# ArduinoShield.net
KiCad netlist of a schematic drawn in EAGLE
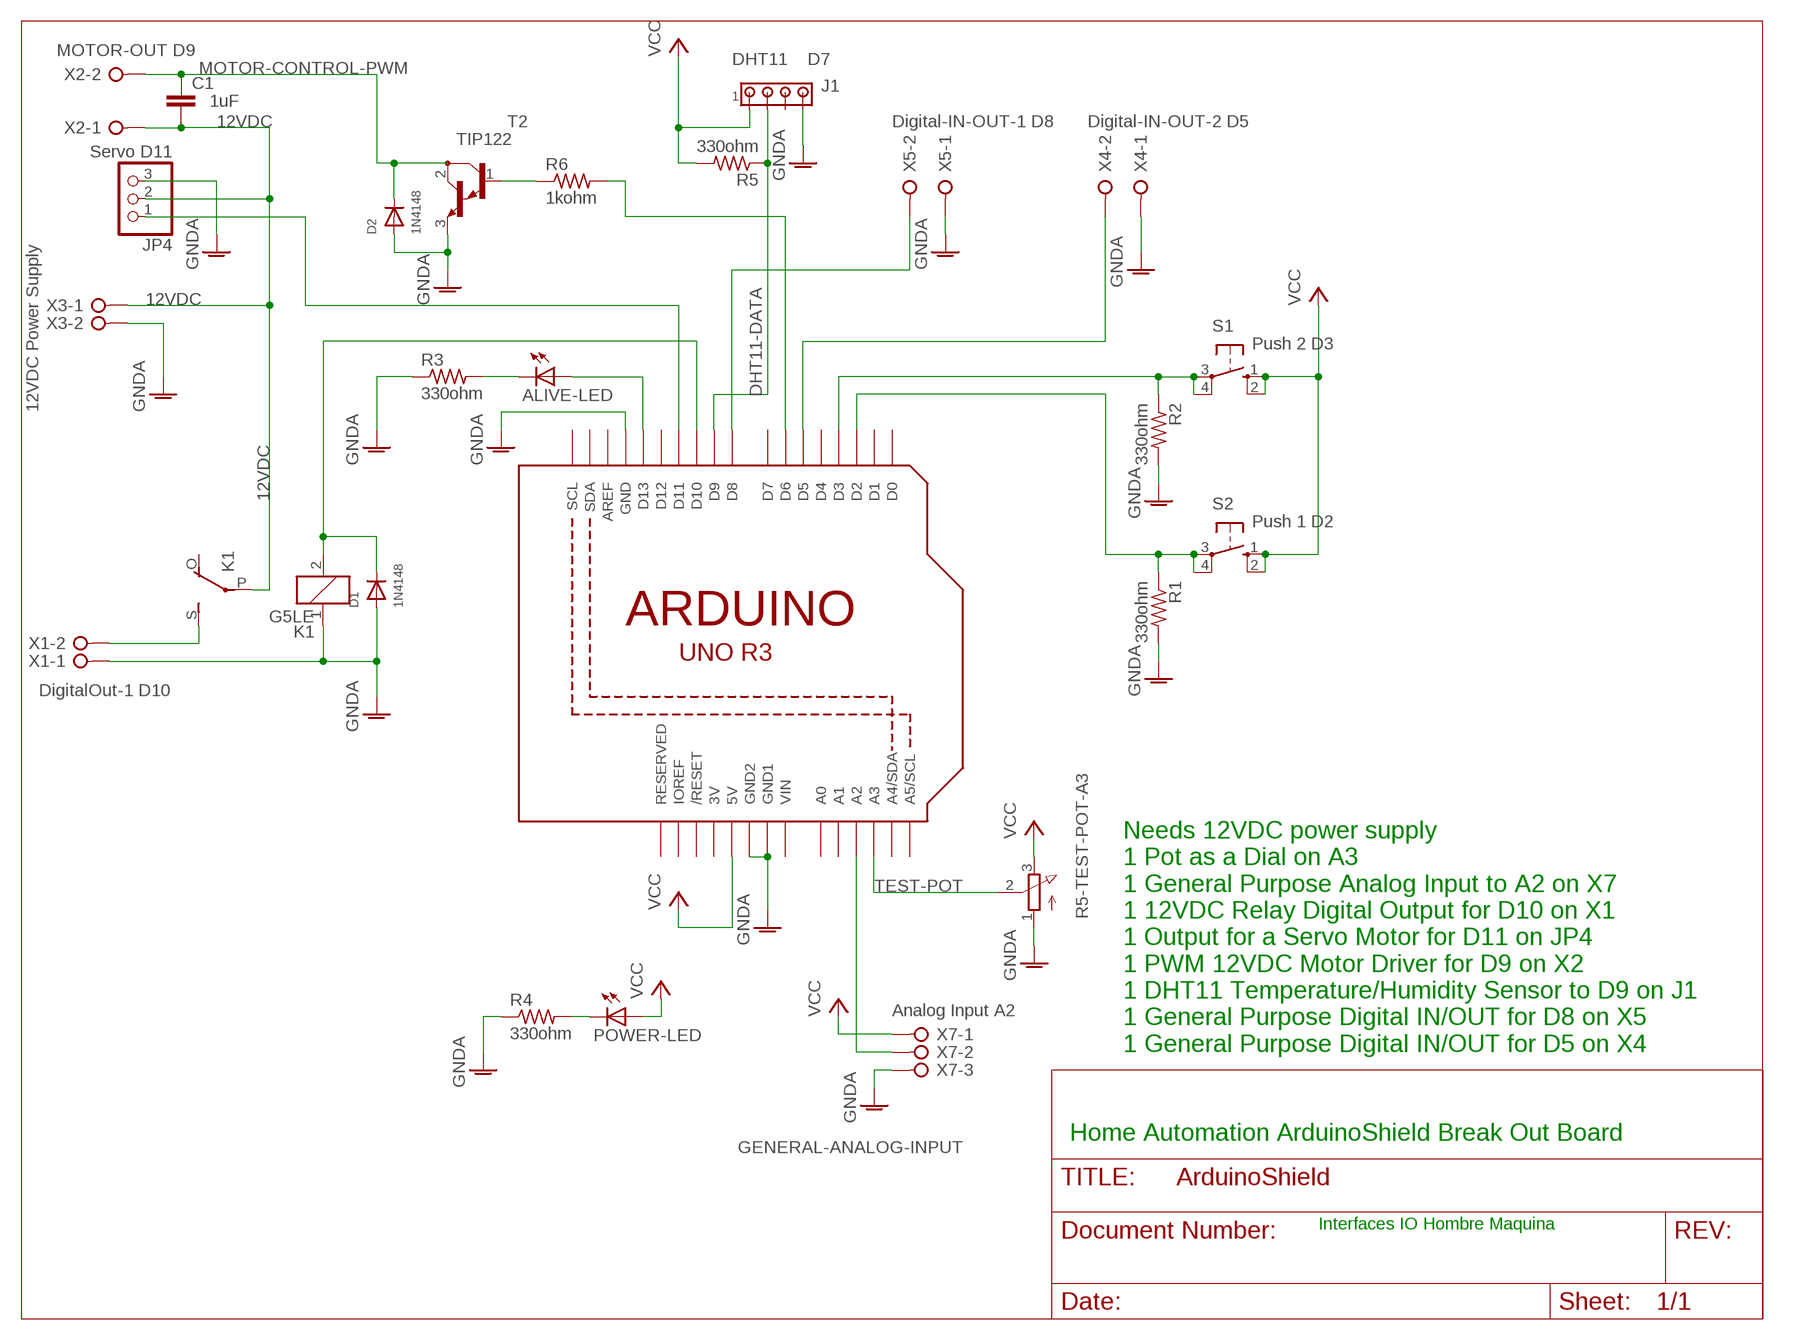
[diagram p0: schematic, sheet 1]

(export (version "E")
  (design (tool "Eeschema 10.0.6"))
  (components
    (comp (ref "ALIVE-LED")
      (value "LED5MM")
      (footprint "eagle-import:LED5MM")
      (libsource (lib "eagle-import") (part "LED5MM"))
    )
    (comp (ref "C1")
      (value "1uF")
      (footprint "eagle-import:C5B3")
      (libsource (lib "eagle-import") (part "C5/3"))
    )
    (comp (ref "D1")
      (value "1N4148")
      (footprint "eagle-import:DO-1N4148")
      (libsource (lib "eagle-import") (part "DIODEDO-1N4148"))
    )
    (comp (ref "D2")
      (value "1N4148")
      (footprint "eagle-import:DO-1N4148")
      (libsource (lib "eagle-import") (part "DIODEDO-1N4148"))
    )
    (comp (ref "J1")
      (value "DHT11 D7")
      (footprint "eagle-import:10X04MTA")
      (libsource (lib "eagle-import") (part "MTA04-100"))
    )
    (comp (ref "JP4")
      (value "Servo D11")
      (footprint "eagle-import:1X03")
      (libsource (lib "eagle-import") (part "PINHD-1X3"))
    )
    (comp (ref "K1")
      (value "G5LE")
      (footprint "eagle-import:G5LE")
      (libsource (lib "eagle-import") (part "G5LE"))
    )
    (comp (ref "POWER-LED")
      (value "LED5MM")
      (footprint "eagle-import:LED5MM")
      (libsource (lib "eagle-import") (part "LED5MM"))
    )
    (comp (ref "R1")
      (value "330ohm")
      (footprint "eagle-import:0204_7")
      (libsource (lib "eagle-import") (part "R-US_0204/7"))
    )
    (comp (ref "R2")
      (value "330ohm")
      (footprint "eagle-import:0204_7")
      (libsource (lib "eagle-import") (part "R-US_0204/7"))
    )
    (comp (ref "R3")
      (value "330ohm")
      (footprint "eagle-import:0204_7")
      (libsource (lib "eagle-import") (part "R-US_0204/7"))
    )
    (comp (ref "R4")
      (value "330ohm")
      (footprint "eagle-import:0204_7")
      (libsource (lib "eagle-import") (part "R-US_0204/7"))
    )
    (comp (ref "R5")
      (value "330ohm")
      (footprint "eagle-import:0204_7")
      (libsource (lib "eagle-import") (part "R-US_0204/7"))
    )
    (comp (ref "R5-TEST-POT-A3")
      (value "3RP/1610N")
      (footprint "eagle-import:3RP_1610N")
      (libsource (lib "eagle-import") (part "3RP/1610N"))
    )
    (comp (ref "R6")
      (value "1kohm")
      (footprint "eagle-import:0204_7")
      (libsource (lib "eagle-import") (part "R-US_0204/7"))
    )
    (comp (ref "S1")
      (value "Push 2 D3")
      (footprint "eagle-import:B3F-10XX")
      (fields (field (name "MPN") "B3F-1000"))
      (libsource (lib "eagle-import") (part "10-XX"))
    )
    (comp (ref "S2")
      (value "Push 1 D2")
      (footprint "eagle-import:B3F-10XX")
      (fields (field (name "MPN") "B3F-1000"))
      (libsource (lib "eagle-import") (part "10-XX"))
    )
    (comp (ref "T2")
      (value "TIP122")
      (footprint "eagle-import:TO220")
      (libsource (lib "eagle-import") (part "TIP122"))
    )
    (comp (ref "U1")
      (value "ARDUINOR3-DIMENSION")
      (footprint "eagle-import:ARDUINOR3")
      (libsource (lib "eagle-import") (part "ARDUINOR3-DIMENSION"))
    )
    (comp (ref "X1")
      (value "W237-02P")
      (footprint "eagle-import:W237-132")
      (libsource (lib "eagle-import") (part "W237-02P"))
    )
    (comp (ref "X2")
      (value "MOTOR-OUT D9")
      (footprint "eagle-import:W237-132")
      (libsource (lib "eagle-import") (part "W237-02P"))
    )
    (comp (ref "X3")
      (value "W237-02P")
      (footprint "eagle-import:W237-132")
      (libsource (lib "eagle-import") (part "W237-02P"))
    )
    (comp (ref "X4")
      (value "W237-02P")
      (footprint "eagle-import:W237-132")
      (libsource (lib "eagle-import") (part "W237-02P"))
    )
    (comp (ref "X5")
      (value "W237-02P")
      (footprint "eagle-import:W237-132")
      (libsource (lib "eagle-import") (part "W237-02P"))
    )
    (comp (ref "X7")
      (value "GENERAL-ANALOG-INPUT")
      (footprint "eagle-import:W237-133")
      (libsource (lib "eagle-import") (part "W237-03P"))
    )
  )
  (nets
    (net (code "1") (name "/3V") (class "Default")
      (node (ref "U1") (pin "3V") (pinfunction "3V_3V") (pintype "power_in"))
    )
    (net (code "2") (name "/12VDC") (class "Default")
      (node (ref "C1") (pin "2") (pinfunction "2_2") (pintype "passive"))
      (node (ref "JP4") (pin "2") (pinfunction "2_2") (pintype "passive"))
      (node (ref "K1") (pin "P") (pinfunction "P_P") (pintype "passive"))
      (node (ref "X2") (pin "1") (pinfunction "KL_1") (pintype "passive"))
      (node (ref "X3") (pin "1") (pinfunction "KL_1") (pintype "passive"))
    )
    (net (code "3") (name "/DHT11-DATA") (class "Default")
      (node (ref "J1") (pin "2") (pinfunction "2_2") (pintype "passive"))
      (node (ref "R5") (pin "1") (pinfunction "1_1") (pintype "passive"))
      (node (ref "U1") (pin "D9") (pinfunction "D9_D9") (pintype "bidirectional"))
    )
    (net (code "4") (name "/MOTOR-CONTROL-PWM") (class "Default")
      (node (ref "C1") (pin "1") (pinfunction "1_1") (pintype "passive"))
      (node (ref "D2") (pin "C") (pinfunction "C_C") (pintype "passive"))
      (node (ref "T2") (pin "2") (pinfunction "C_2") (pintype "passive"))
      (node (ref "X2") (pin "2") (pinfunction "KL_2") (pintype "passive"))
    )
    (net (code "5") (name "/TEST-POT") (class "Default")
      (node (ref "R5-TEST-POT-A3") (pin "2") (pinfunction "S_2") (pintype "passive"))
      (node (ref "U1") (pin "A3") (pinfunction "A3_A3") (pintype "bidirectional"))
    )
    (net (code "6") (name "/VIN") (class "Default")
      (node (ref "U1") (pin "VIN") (pinfunction "VIN_VIN") (pintype "power_in"))
    )
    (net (code "7") (name "GNDA") (class "Default")
      (node (ref "D1") (pin "A") (pinfunction "A_A") (pintype "passive"))
      (node (ref "D2") (pin "A") (pinfunction "A_A") (pintype "passive"))
      (node (ref "J1") (pin "4") (pinfunction "4_4") (pintype "passive"))
      (node (ref "JP4") (pin "3") (pinfunction "3_3") (pintype "passive"))
      (node (ref "K1") (pin "1") (pinfunction "1_1") (pintype "passive"))
      (node (ref "R1") (pin "2") (pinfunction "2_2") (pintype "passive"))
      (node (ref "R2") (pin "2") (pinfunction "2_2") (pintype "passive"))
      (node (ref "R3") (pin "1") (pinfunction "1_1") (pintype "passive"))
      (node (ref "R4") (pin "1") (pinfunction "1_1") (pintype "passive"))
      (node (ref "R5-TEST-POT-A3") (pin "1") (pinfunction "A_1") (pintype "passive"))
      (node (ref "T2") (pin "3") (pinfunction "E_3") (pintype "passive"))
      (node (ref "U1") (pin "GND") (pinfunction "GND_GND") (pintype "power_in"))
      (node (ref "U1") (pin "GND1") (pinfunction "GND1_GND1") (pintype "power_in"))
      (node (ref "U1") (pin "GND2") (pinfunction "GND2_GND2") (pintype "power_in"))
      (node (ref "X1") (pin "1") (pinfunction "KL_1") (pintype "passive"))
      (node (ref "X3") (pin "2") (pinfunction "KL_2") (pintype "passive"))
      (node (ref "X4") (pin "1") (pinfunction "KL_1") (pintype "passive"))
      (node (ref "X5") (pin "1") (pinfunction "KL_1") (pintype "passive"))
      (node (ref "X7") (pin "3") (pinfunction "KL_3") (pintype "passive"))
    )
    (net (code "8") (name "Net-(ALIVE-LED-C)") (class "Default")
      (node (ref "ALIVE-LED") (pin "K") (pinfunction "C_K") (pintype "passive"))
      (node (ref "R3") (pin "2") (pinfunction "2_2") (pintype "passive"))
    )
    (net (code "9") (name "Net-(ALIVE-LED-PadA)") (class "Default")
      (node (ref "ALIVE-LED") (pin "A") (pinfunction "A_A") (pintype "passive"))
      (node (ref "U1") (pin "D13") (pinfunction "D13_D13") (pintype "bidirectional"))
    )
    (net (code "10") (name "Net-(D1-PadC)") (class "Default")
      (node (ref "D1") (pin "C") (pinfunction "C_C") (pintype "passive"))
      (node (ref "K1") (pin "2") (pinfunction "2_2") (pintype "passive"))
      (node (ref "U1") (pin "D10") (pinfunction "D10_D10") (pintype "bidirectional"))
    )
    (net (code "11") (name "Net-(JP4-Pad1)") (class "Default")
      (node (ref "JP4") (pin "1") (pinfunction "1_1") (pintype "passive"))
      (node (ref "U1") (pin "D11") (pinfunction "D11_D11") (pintype "bidirectional"))
    )
    (net (code "12") (name "Net-(POWER-LED-C)") (class "Default")
      (node (ref "POWER-LED") (pin "K") (pinfunction "C_K") (pintype "passive"))
      (node (ref "R4") (pin "2") (pinfunction "2_2") (pintype "passive"))
    )
    (net (code "13") (name "Net-(R6-Pad2)") (class "Default")
      (node (ref "R6") (pin "2") (pinfunction "2_2") (pintype "passive"))
      (node (ref "U1") (pin "D6") (pinfunction "D6_D6") (pintype "bidirectional"))
    )
    (net (code "14") (name "Net-(S1-P)") (class "Default")
      (node (ref "R2") (pin "1") (pinfunction "1_1") (pintype "passive"))
      (node (ref "S1") (pin "3") (pinfunction "P_3") (pintype "passive"))
      (node (ref "S1") (pin "4") (pinfunction "P1_4") (pintype "passive"))
      (node (ref "U1") (pin "D3") (pinfunction "D3_D3") (pintype "bidirectional"))
    )
    (net (code "15") (name "Net-(S2-P)") (class "Default")
      (node (ref "R1") (pin "1") (pinfunction "1_1") (pintype "passive"))
      (node (ref "S2") (pin "3") (pinfunction "P_3") (pintype "passive"))
      (node (ref "S2") (pin "4") (pinfunction "P1_4") (pintype "passive"))
      (node (ref "U1") (pin "D2") (pinfunction "D2_D2") (pintype "bidirectional"))
    )
    (net (code "16") (name "Net-(T2-B)") (class "Default")
      (node (ref "R6") (pin "1") (pinfunction "1_1") (pintype "passive"))
      (node (ref "T2") (pin "1") (pinfunction "B_1") (pintype "passive"))
    )
    (net (code "17") (name "Net-(X1B-KL)") (class "Default")
      (node (ref "K1") (pin "S") (pinfunction "S_S") (pintype "passive"))
      (node (ref "X1") (pin "2") (pinfunction "KL_2") (pintype "passive"))
    )
    (net (code "18") (name "Net-(X4B-KL)") (class "Default")
      (node (ref "U1") (pin "D5") (pinfunction "D5_D5") (pintype "bidirectional"))
      (node (ref "X4") (pin "2") (pinfunction "KL_2") (pintype "passive"))
    )
    (net (code "19") (name "Net-(X5B-KL)") (class "Default")
      (node (ref "U1") (pin "D8") (pinfunction "D8_D8") (pintype "bidirectional"))
      (node (ref "X5") (pin "2") (pinfunction "KL_2") (pintype "passive"))
    )
    (net (code "20") (name "Net-(X7B-KL)") (class "Default")
      (node (ref "U1") (pin "A2") (pinfunction "A2_A2") (pintype "bidirectional"))
      (node (ref "X7") (pin "2") (pinfunction "KL_2") (pintype "passive"))
    )
    (net (code "21") (name "VCC") (class "Default")
      (node (ref "J1") (pin "1") (pinfunction "1_1") (pintype "passive"))
      (node (ref "POWER-LED") (pin "A") (pinfunction "A_A") (pintype "passive"))
      (node (ref "R5") (pin "2") (pinfunction "2_2") (pintype "passive"))
      (node (ref "R5-TEST-POT-A3") (pin "3") (pinfunction "E_3") (pintype "passive"))
      (node (ref "S1") (pin "1") (pinfunction "S_1") (pintype "passive"))
      (node (ref "S1") (pin "2") (pinfunction "S1_2") (pintype "passive"))
      (node (ref "S2") (pin "1") (pinfunction "S_1") (pintype "passive"))
      (node (ref "S2") (pin "2") (pinfunction "S1_2") (pintype "passive"))
      (node (ref "U1") (pin "5V") (pinfunction "5V_5V") (pintype "power_in"))
      (node (ref "X7") (pin "1") (pinfunction "KL_1") (pintype "passive"))
    )
    (net (code "22") (name "unconnected-(J1-Pad3)") (class "Default")
      (node (ref "J1") (pin "3") (pinfunction "3_3") (pintype "passive"))
    )
    (net (code "23") (name "unconnected-(K1-PadO)") (class "Default")
      (node (ref "K1") (pin "O") (pinfunction "O_O") (pintype "passive"))
    )
    (net (code "24") (name "unconnected-(U1-A4{slash}SDA-PadA4)") (class "Default")
      (node (ref "U1") (pin "A4") (pinfunction "A4/SDA_A4") (pintype "bidirectional"))
    )
    (net (code "25") (name "unconnected-(U1-A5{slash}SCL-PadA5)") (class "Default")
      (node (ref "U1") (pin "A5") (pinfunction "A5/SCL_A5") (pintype "bidirectional"))
    )
    (net (code "26") (name "unconnected-(U1-PadA0)") (class "Default")
      (node (ref "U1") (pin "A0") (pinfunction "A0_A0") (pintype "bidirectional"))
    )
    (net (code "27") (name "unconnected-(U1-PadA1)") (class "Default")
      (node (ref "U1") (pin "A1") (pinfunction "A1_A1") (pintype "bidirectional"))
    )
    (net (code "28") (name "unconnected-(U1-PadAREF)") (class "Default")
      (node (ref "U1") (pin "AREF") (pinfunction "AREF_AREF") (pintype "bidirectional"))
    )
    (net (code "29") (name "unconnected-(U1-PadD0)") (class "Default")
      (node (ref "U1") (pin "D0") (pinfunction "D0_D0") (pintype "bidirectional"))
    )
    (net (code "30") (name "unconnected-(U1-PadD1)") (class "Default")
      (node (ref "U1") (pin "D1") (pinfunction "D1_D1") (pintype "bidirectional"))
    )
    (net (code "31") (name "unconnected-(U1-PadD4)") (class "Default")
      (node (ref "U1") (pin "D4") (pinfunction "D4_D4") (pintype "bidirectional"))
    )
    (net (code "32") (name "unconnected-(U1-PadD7)") (class "Default")
      (node (ref "U1") (pin "D7") (pinfunction "D7_D7") (pintype "bidirectional"))
    )
    (net (code "33") (name "unconnected-(U1-PadD12)") (class "Default")
      (node (ref "U1") (pin "D12") (pinfunction "D12_D12") (pintype "bidirectional"))
    )
    (net (code "34") (name "unconnected-(U1-PadIOREF)") (class "Default")
      (node (ref "U1") (pin "IOREF") (pinfunction "IOREF_IOREF") (pintype "output"))
    )
    (net (code "35") (name "unconnected-(U1-PadRESERVED)") (class "Default")
      (node (ref "U1") (pin "RESERVED") (pinfunction "RESERVED_RESERVED") (pintype "no_connect"))
    )
    (net (code "36") (name "unconnected-(U1-PadSCL)") (class "Default")
      (node (ref "U1") (pin "SCL") (pinfunction "SCL_SCL") (pintype "bidirectional"))
    )
    (net (code "37") (name "unconnected-(U1-PadSDA)") (class "Default")
      (node (ref "U1") (pin "SDA") (pinfunction "SDA_SDA") (pintype "bidirectional"))
    )
    (net (code "38") (name "unconnected-(U1-{slash}RESET-PadRESET)") (class "Default")
      (node (ref "U1") (pin "RESET") (pinfunction "/RESET_RESET") (pintype "bidirectional"))
    )
  )
)
